# VCO.net
KiCad netlist of a schematic drawn in Altium Designer
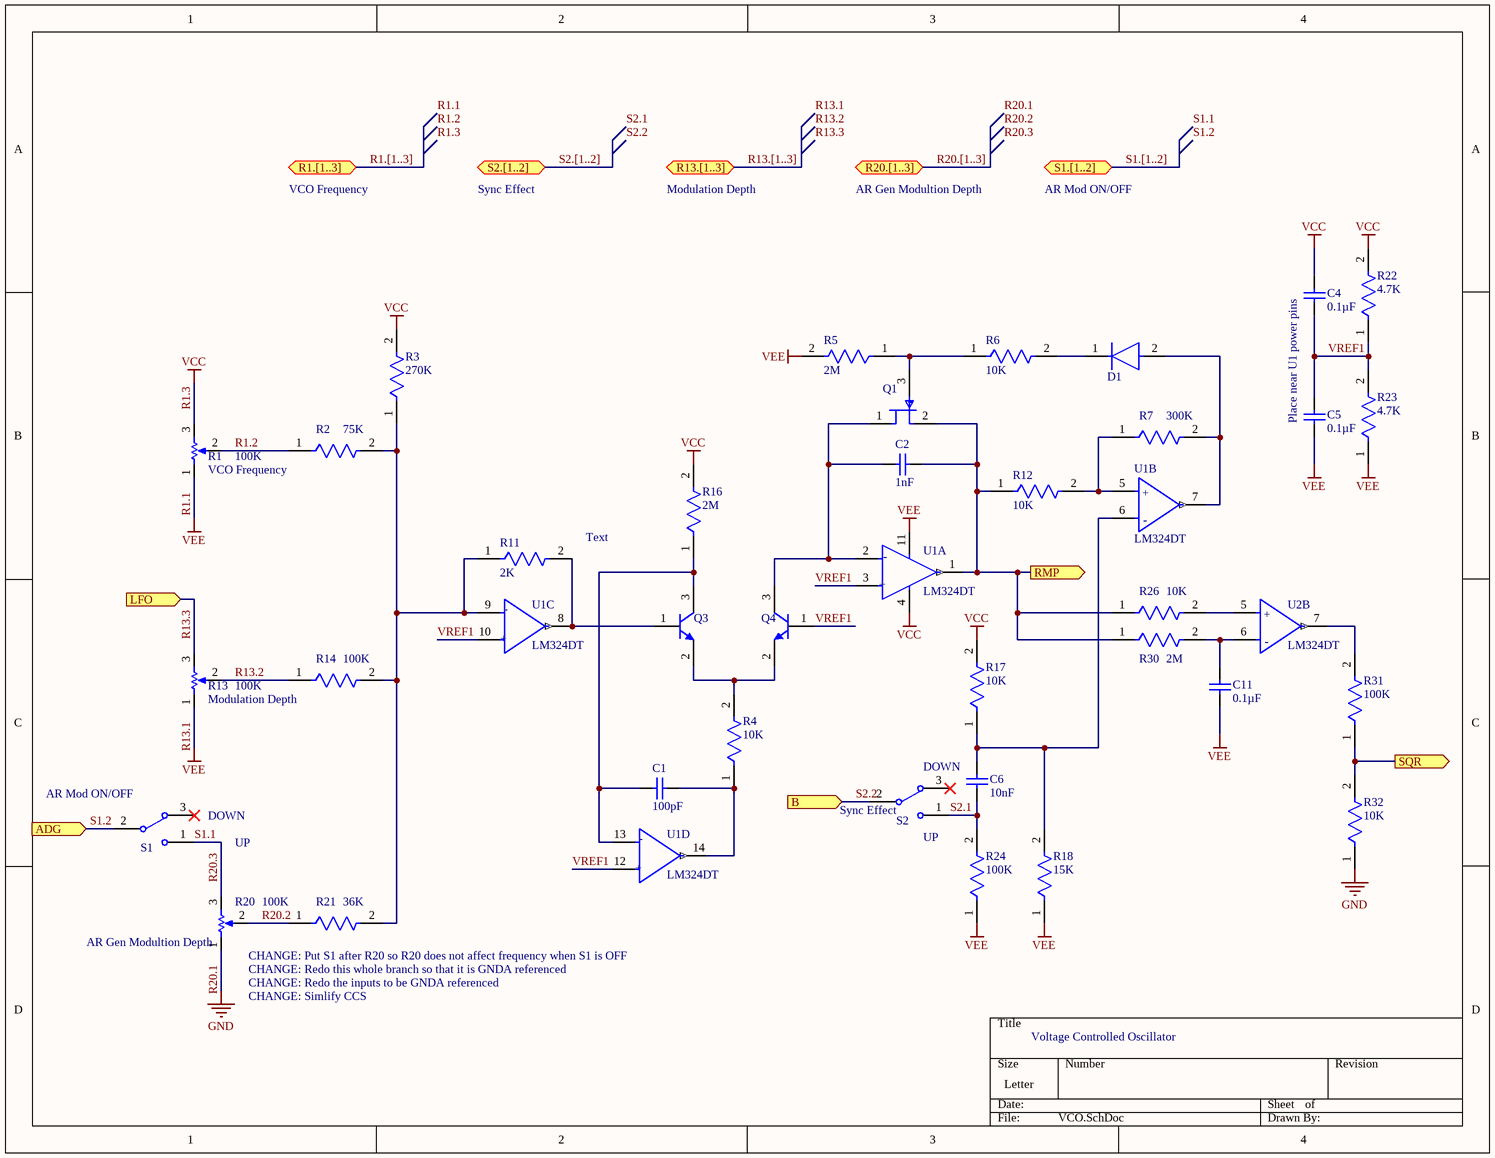
[diagram p0: VCO.SchDoc]

(export (version "E")
  (design (tool "Eeschema 10.0.6"))
  (components
    (comp (ref "C1")
      (value "885012206077‎")
      (footprint "CAPC1608X90X35NL10T15")
      (fields
        (field (name "PART NUMBER") "885012206083‎")
        (field (name "MANUFACTURER") "Wurth")
        (field (name "MANUFACTURER PART NUMBER") "885012206083")
        (field (name "CAPACITANCE") "100pF")
      )
      (libsource (lib "Altium Content Vault") (part "CAP"))
    )
    (comp (ref "C2")
      (value "885012206083‎")
      (footprint "CAPC1608X90X35NL10T15")
      (fields
        (field (name "MANUFACTURER") "Wurth")
        (field (name "MANUFACTURER PART NUMBER") "885012206083")
        (field (name "CAPACITANCE") "1nF")
        (field (name "TOLERANCE") "10%")
      )
      (libsource (lib "Altium Content Vault") (part "CAP"))
    )
    (comp (ref "C4")
      (value "CL10B104KB8NNNC")
      (footprint "SAMS-C0603-2_M")
      (description "Multi-layer Ceramic Capacitor, -55 to 125 degC, 2-Pin SMD (0603), RoHS, Tape and Reel")
      (fields (field (name "CAPACITANCE") "0.1µF") (field (name "MANUFACTURER") "Samsung Electro-Mechanics"))
      (libsource (lib "Altium Content Vault") (part "CAP-NP-2"))
    )
    (comp (ref "C5")
      (value "CL10B104KB8NNNC")
      (footprint "SAMS-C0603-2_M")
      (description "Multi-layer Ceramic Capacitor, -55 to 125 degC, 2-Pin SMD (0603), RoHS, Tape and Reel")
      (fields (field (name "CAPACITANCE") "0.1µF") (field (name "MANUFACTURER") "Samsung Electro-Mechanics"))
      (libsource (lib "Altium Content Vault") (part "CAP-NP-2"))
    )
    (comp (ref "C6")
      (value "885012206089")
      (footprint "CAPC1608X90X35NL10T15")
      (fields
        (field (name "MANUFACTURER") "Wurth Electronics")
        (field (name "CAPACITANCE") "10nF")
        (field (name "TOLERANCE") "10%")
      )
      (libsource (lib "Altium Content Vault") (part "CAP"))
    )
    (comp (ref "C11")
      (value "CL10B104KB8NNNC")
      (footprint "SAMS-C0603-2_M")
      (description "Multi-layer Ceramic Capacitor, -55 to 125 degC, 2-Pin SMD (0603), RoHS, Tape and Reel")
      (fields (field (name "CAPACITANCE") "0.1µF") (field (name "MANUFACTURER") "Samsung Electro-Mechanics"))
      (libsource (lib "Altium Content Vault") (part "CAP-NP-2"))
    )
    (comp (ref "D1")
      (value "1N4448WS-7-F")
      (footprint "FP-SOD323-MFG")
      (description "DIODE GEN PURP 75V 250MA SOD323")
      (fields
        (field (name "MANUFACTURER") "Diodes Incorporated")
        (field (name "OCTOPART") "https://octopart.com/1n4448ws-7-f-diodes+inc.-55389585")
      )
      (libsource (lib "Altium Content Vault") (part "d7152d700b627762746794eb795d46e"))
    )
    (comp (ref "Q1")
      (value "MMBFJ113")
      (footprint "FP-318BM-IPC_C")
      (description "JFET N-CH 35V 350MW SOT23")
      (fields
        (field (name "MANUFACTURER") "ON Semiconductor")
        (field (name "OCTOPART") "https://octopart.com/mmbfj113-on+semiconductor-84330253")
      )
      (libsource (lib "Altium Content Vault") (part "14398f7355be6f33287877db3ee21c7"))
    )
    (comp (ref "Q3")
      (value "MMBT3904LT1G")
      (footprint "ONSC-SOT-23-3-318-08_V")
      (description "General Purpose Transistor, NPN Silicon, 3-Pin SOT-23, Pb-Free, Tape and Reel")
      (fields
        (field (name "MANUFACTURER") "On Semiconductor")
        (field (name "MANUFACTURER PART NUMBER") "MMBT3904,215")
      )
      (libsource (lib "Altium Content Vault") (part "ONSC-NPN-B1E2C3-3"))
    )
    (comp (ref "Q4")
      (value "MMBT3904LT1G")
      (footprint "ONSC-SOT-23-3-318-08_V")
      (description "General Purpose Transistor, NPN Silicon, 3-Pin SOT-23, Pb-Free, Tape and Reel")
      (fields
        (field (name "MANUFACTURER") "On Semiconductor")
        (field (name "MANUFACTURER PART NUMBER") "MMBT3904,215")
      )
      (libsource (lib "Altium Content Vault") (part "ONSC-NPN-B1E2C3-3"))
    )
    (comp (ref "R1")
      (value "VCO Frequency")
      (footprint "VR5")
      (description "Potentiometer")
      (fields (field (name "ALTIUM_VALUE") "100K") (field (name "PUBLISHER") "Altium Limited"))
      (libsource (lib "Miscellaneous Devices") (part "RPot"))
    )
    (comp (ref "R2")
      (value "ESR03EZPJ753")
      (footprint "FP-ESR03-IPC_B")
      (description "75kΩ ±5% 0.25W 0603 Anti-Surge Chip Resistor AEC-Q200")
      (fields (field (name "TOLERANCE") "5%") (field (name "RESISTANCE") "75K"))
      (libsource (lib "Altium Content Vault") (part "1029c3af85768c4190bb7ad29bc67b5"))
    )
    (comp (ref "R3")
      (value "ESR03EZPJ274")
      (footprint "FP-ESR03-IPC_B")
      (description "270kΩ ±5% 0.25W 0603 Anti-Surge Chip Resistor AEC-Q200")
      (fields (field (name "RESISTANCE") "270K") (field (name "TOLERANCE") "5%"))
      (libsource (lib "Altium Content Vault") (part "1029c3af85768c4190bb7ad29bc67b5"))
    )
    (comp (ref "R4")
      (value "ESR03EZPJ103")
      (footprint "FP-ESR03-IPC_B")
      (description "10kΩ ±5% 0.25W 0603 Anti-Surge Chip Resistor AEC-Q200")
      (fields (field (name "TOLERANCE") "5%") (field (name "RESISTANCE") "10K"))
      (libsource (lib "Altium Content Vault") (part "1029c3af85768c4190bb7ad29bc67b5"))
    )
    (comp (ref "R5")
      (value "ESR03EZPJ205")
      (footprint "FP-ESR03-IPC_B")
      (description "2MΩ ±5% 0.25W 0603 Anti-Surge Chip Resistor AEC-Q200")
      (fields (field (name "TOLERANCE") "5%") (field (name "RESISTANCE") "2M"))
      (libsource (lib "Altium Content Vault") (part "1029c3af85768c4190bb7ad29bc67b5"))
    )
    (comp (ref "R6")
      (value "ESR03EZPJ103")
      (footprint "FP-ESR03-IPC_B")
      (description "10kΩ ±5% 0.25W 0603 Anti-Surge Chip Resistor AEC-Q200")
      (fields (field (name "TOLERANCE") "5%") (field (name "RESISTANCE") "10K"))
      (libsource (lib "Altium Content Vault") (part "1029c3af85768c4190bb7ad29bc67b5"))
    )
    (comp (ref "R7")
      (value "ESR03EZPJ304")
      (footprint "FP-ESR03-IPC_B")
      (description "300kΩ ±5% 0.25W 0603 Anti-Surge Chip Resistor AEC-Q200")
      (fields (field (name "TOLERANCE") "5%") (field (name "RESISTANCE") "300K"))
      (libsource (lib "Altium Content Vault") (part "1029c3af85768c4190bb7ad29bc67b5"))
    )
    (comp (ref "R11")
      (value "ESR03EZPJ202")
      (footprint "FP-ESR03-IPC_B")
      (description "2kΩ ±5% 0.25W 0603 Anti-Surge Chip Resistor AEC-Q200")
      (fields (field (name "RESISTANCE") "2K") (field (name "TOLERANCE") "5%"))
      (libsource (lib "Altium Content Vault") (part "1029c3af85768c4190bb7ad29bc67b5"))
    )
    (comp (ref "R12")
      (value "ESR03EZPJ103")
      (footprint "FP-ESR03-IPC_B")
      (description "10kΩ ±5% 0.25W 0603 Anti-Surge Chip Resistor AEC-Q200")
      (fields (field (name "TOLERANCE") "5%") (field (name "RESISTANCE") "10K"))
      (libsource (lib "Altium Content Vault") (part "1029c3af85768c4190bb7ad29bc67b5"))
    )
    (comp (ref "R13")
      (value "Modulation Depth")
      (footprint "VR5")
      (description "Potentiometer")
      (fields (field (name "ALTIUM_VALUE") "100K") (field (name "PUBLISHER") "Altium Limited"))
      (libsource (lib "Miscellaneous Devices") (part "RPot"))
    )
    (comp (ref "R14")
      (value "ESR03EZPJ104")
      (footprint "FP-ESR03-IPC_B")
      (description "100kΩ ±5% 0.25W 0603 Anti-Surge Chip Resistor AEC-Q200")
      (fields (field (name "TOLERANCE") "5%") (field (name "RESISTANCE") "100K"))
      (libsource (lib "Altium Content Vault") (part "1029c3af85768c4190bb7ad29bc67b5"))
    )
    (comp (ref "R16")
      (value "ESR03EZPJ205")
      (footprint "FP-ESR03-IPC_B")
      (description "2MΩ ±5% 0.25W 0603 Anti-Surge Chip Resistor AEC-Q200")
      (fields (field (name "TOLERANCE") "5%") (field (name "RESISTANCE") "2M"))
      (libsource (lib "Altium Content Vault") (part "1029c3af85768c4190bb7ad29bc67b5"))
    )
    (comp (ref "R17")
      (value "ESR03EZPJ103")
      (footprint "FP-ESR03-IPC_B")
      (description "10kΩ ±5% 0.25W 0603 Anti-Surge Chip Resistor AEC-Q200")
      (fields (field (name "TOLERANCE") "5%") (field (name "RESISTANCE") "10K"))
      (libsource (lib "Altium Content Vault") (part "1029c3af85768c4190bb7ad29bc67b5"))
    )
    (comp (ref "R18")
      (value "ESR03EZPJ153")
      (footprint "FP-ESR03-IPC_B")
      (description "15kΩ ±5% 0.25W 0603 Anti-Surge Chip Resistor AEC-Q200")
      (fields (field (name "RESISTANCE") "15K") (field (name "TOLERANCE") "5%"))
      (libsource (lib "Altium Content Vault") (part "1029c3af85768c4190bb7ad29bc67b5"))
    )
    (comp (ref "R20")
      (value "AR Gen Modultion Depth")
      (footprint "VR5")
      (description "Potentiometer")
      (fields (field (name "ALTIUM_VALUE") "100K") (field (name "PUBLISHER") "Altium Limited"))
      (libsource (lib "Miscellaneous Devices") (part "RPot"))
    )
    (comp (ref "R21")
      (value "ESR03EZPJ363")
      (footprint "FP-ESR03-IPC_B")
      (description "36kΩ ±5% 0.25W 0603 Anti-Surge Chip Resistor AEC-Q200")
      (fields (field (name "TOLERANCE") "5%") (field (name "RESISTANCE") "36K"))
      (libsource (lib "Altium Content Vault") (part "1029c3af85768c4190bb7ad29bc67b5"))
    )
    (comp (ref "R22")
      (value "ESR03EZPJ472")
      (footprint "FP-ESR03-IPC_B")
      (description "4.7kΩ ±5% 0.25W 0603 Anti-Surge Chip Resistor AEC-Q200")
      (fields (field (name "TOLERANCE") "5%") (field (name "RESISTANCE") "4.7K"))
      (libsource (lib "Altium Content Vault") (part "1029c3af85768c4190bb7ad29bc67b5"))
    )
    (comp (ref "R23")
      (value "ESR03EZPJ472")
      (footprint "FP-ESR03-IPC_B")
      (description "4.7kΩ ±5% 0.25W 0603 Anti-Surge Chip Resistor AEC-Q200")
      (fields (field (name "TOLERANCE") "5%") (field (name "RESISTANCE") "4.7K"))
      (libsource (lib "Altium Content Vault") (part "1029c3af85768c4190bb7ad29bc67b5"))
    )
    (comp (ref "R24")
      (value "ESR03EZPJ104")
      (footprint "FP-ESR03-IPC_B")
      (description "100kΩ ±5% 0.25W 0603 Anti-Surge Chip Resistor AEC-Q200")
      (fields (field (name "TOLERANCE") "5%") (field (name "RESISTANCE") "100K"))
      (libsource (lib "Altium Content Vault") (part "1029c3af85768c4190bb7ad29bc67b5"))
    )
    (comp (ref "R26")
      (value "ESR03EZPJ103")
      (footprint "FP-ESR03-IPC_B")
      (description "10kΩ ±5% 0.25W 0603 Anti-Surge Chip Resistor AEC-Q200")
      (fields (field (name "TOLERANCE") "5%") (field (name "RESISTANCE") "10K"))
      (libsource (lib "Altium Content Vault") (part "1029c3af85768c4190bb7ad29bc67b5"))
    )
    (comp (ref "R30")
      (value "ESR03EZPJ205")
      (footprint "FP-ESR03-IPC_B")
      (description "2MΩ ±5% 0.25W 0603 Anti-Surge Chip Resistor AEC-Q200")
      (fields (field (name "TOLERANCE") "5%") (field (name "RESISTANCE") "2M"))
      (libsource (lib "Altium Content Vault") (part "1029c3af85768c4190bb7ad29bc67b5"))
    )
    (comp (ref "R31")
      (value "ESR03EZPJ104")
      (footprint "FP-ESR03-IPC_B")
      (description "100kΩ ±5% 0.25W 0603 Anti-Surge Chip Resistor AEC-Q200")
      (fields (field (name "TOLERANCE") "5%") (field (name "RESISTANCE") "100K"))
      (libsource (lib "Altium Content Vault") (part "1029c3af85768c4190bb7ad29bc67b5"))
    )
    (comp (ref "R32")
      (value "ESR03EZPJ103")
      (footprint "FP-ESR03-IPC_B")
      (description "10kΩ ±5% 0.25W 0603 Anti-Surge Chip Resistor AEC-Q200")
      (fields (field (name "TOLERANCE") "5%") (field (name "RESISTANCE") "10K"))
      (libsource (lib "Altium Content Vault") (part "1029c3af85768c4190bb7ad29bc67b5"))
    )
    (comp (ref "S1")
      (value "AR Mod ON/OFF")
      (footprint "HDR1X3")
      (description "Switch Toggle ON None ON SPDT Round Lever Solder Lug 5A 250VAC 28VDC Panel Mount with Threads")
      (fields
        (field (name "MANUFACTURER") "E-Switch")
        (field (name "MANUFACTURER PART NUMBER") "100SP1T1B1M1QEH")
      )
      (libsource (lib "Miscellaneous Devices") (part "SW-SPDT"))
    )
    (comp (ref "S2")
      (value "Sync Effect")
      (footprint "HDR1X3")
      (description "Switch Toggle ON None ON SPDT Round Lever Solder Lug 5A 250VAC 28VDC Panel Mount with Threads")
      (fields
        (field (name "MANUFACTURER") "E-Switch")
        (field (name "MANUFACTURER PART NUMBER") "100SP1T1B1M1QEH")
      )
      (libsource (lib "Miscellaneous Devices") (part "SW-SPDT"))
    )
    (comp (ref "U1")
      (value "LM324DT")
      (footprint "FP-SO-14-MFG")
      (description "IC OPAMP GP 4 CIRCUIT 14SO")
      (fields
        (field (name "OCTOPART") "https://octopart.com/lm324dt-stmicroelectronics-39579146")
        (field (name "MANUFACTURER") "STMicroelectronics")
      )
      (libsource (lib "Altium Content Vault") (part "a065ef67e5aa9ef3942d43d6008d043"))
    )
    (comp (ref "U2")
      (value "LM324DT")
      (footprint "FP-SO-14-MFG")
      (description "IC OPAMP GP 4 CIRCUIT 14SO")
      (fields
        (field (name "OCTOPART") "https://octopart.com/lm324dt-stmicroelectronics-39579146")
        (field (name "MANUFACTURER") "STMicroelectronics")
      )
      (libsource (lib "Altium Content Vault") (part "a065ef67e5aa9ef3942d43d6008d043"))
    )
  )
  (nets
    (net (code "1") (name "/R1.2") (class "Default")
      (node (ref "R1") (pin "2") (pinfunction "TAP_2") (pintype "passive"))
      (node (ref "R2") (pin "1") (pinfunction "1_1") (pintype "passive"))
    )
    (net (code "3") (name "/R13.2") (class "Default")
      (node (ref "R13") (pin "2") (pinfunction "TAP_2") (pintype "passive"))
      (node (ref "R14") (pin "1") (pinfunction "1_1") (pintype "passive"))
    )
    (net (code "4") (name "/R13.3") (class "Default")
      (node (ref "R13") (pin "3") (pinfunction "BOT_3") (pintype "passive"))
    )
    (net (code "6") (name "/R20.2") (class "Default")
      (node (ref "R20") (pin "2") (pinfunction "TAP_2") (pintype "passive"))
      (node (ref "R21") (pin "1") (pinfunction "1_1") (pintype "passive"))
    )
    (net (code "8") (name "/RMP") (class "Default")
      (node (ref "C2") (pin "2") (pinfunction "2_2") (pintype "passive"))
      (node (ref "Q1") (pin "2") (pinfunction "S_2") (pintype "passive"))
      (node (ref "R12") (pin "1") (pinfunction "1_1") (pintype "passive"))
      (node (ref "R26") (pin "1") (pinfunction "1_1") (pintype "passive"))
      (node (ref "R30") (pin "1") (pinfunction "1_1") (pintype "passive"))
      (node (ref "U1") (pin "1") (pinfunction "Output_1_1") (pintype "output"))
    )
    (net (code "9") (name "/S1.1") (class "Default")
      (node (ref "R20") (pin "3") (pinfunction "BOT_3") (pintype "passive"))
      (node (ref "S1") (pin "1") (pinfunction "1_1") (pintype "passive"))
    )
    (net (code "10") (name "/S1.2") (class "Default")
      (node (ref "S1") (pin "2") (pinfunction "2_2") (pintype "passive"))
    )
    (net (code "12") (name "/S2.1") (class "Default")
      (node (ref "C6") (pin "1") (pinfunction "1_1") (pintype "passive"))
      (node (ref "R24") (pin "2") (pinfunction "2_2") (pintype "passive"))
      (node (ref "S2") (pin "1") (pinfunction "1_1") (pintype "passive"))
    )
    (net (code "13") (name "/S2.2") (class "Default")
      (node (ref "S2") (pin "2") (pinfunction "2_2") (pintype "passive"))
    )
    (net (code "15") (name "/SQR") (class "Default")
      (node (ref "R31") (pin "1") (pinfunction "1_1") (pintype "passive"))
      (node (ref "R32") (pin "2") (pinfunction "2_2") (pintype "passive"))
    )
    (net (code "16") (name "/VREF1") (class "Default")
      (node (ref "C4") (pin "2") (pinfunction "2_2") (pintype "passive"))
      (node (ref "C5") (pin "1") (pinfunction "1_1") (pintype "passive"))
      (node (ref "Q4") (pin "1") (pinfunction "B_1") (pintype "passive"))
      (node (ref "R22") (pin "1") (pinfunction "1_1") (pintype "passive"))
      (node (ref "R23") (pin "2") (pinfunction "2_2") (pintype "passive"))
      (node (ref "U1") (pin "10") (pinfunction "Non-Inverting_Input_3_10") (pintype "tri_state"))
      (node (ref "U1") (pin "12") (pinfunction "Non-Inverting_Input_4_12") (pintype "tri_state"))
      (node (ref "U1") (pin "3") (pinfunction "Non-Inverting_Input_1_3") (pintype "tri_state"))
    )
    (net (code "17") (name "GND") (class "Default")
      (node (ref "R20") (pin "1") (pinfunction "TOP_1") (pintype "passive"))
      (node (ref "R32") (pin "1") (pinfunction "1_1") (pintype "passive"))
    )
    (net (code "18") (name "Net-(D1-A)") (class "Default")
      (node (ref "D1") (pin "2") (pinfunction "A_2") (pintype "passive"))
      (node (ref "R7") (pin "2") (pinfunction "2_2") (pintype "passive"))
      (node (ref "U1") (pin "7") (pinfunction "Output_2_7") (pintype "output"))
    )
    (net (code "19") (name "Net-(D1-C)") (class "Default")
      (node (ref "D1") (pin "1") (pinfunction "C_1") (pintype "passive"))
      (node (ref "R6") (pin "2") (pinfunction "2_2") (pintype "passive"))
    )
    (net (code "20") (name "Net-(Q1-D)") (class "Default")
      (node (ref "C2") (pin "1") (pinfunction "1_1") (pintype "passive"))
      (node (ref "Q1") (pin "1") (pinfunction "D_1") (pintype "passive"))
      (node (ref "Q4") (pin "3") (pinfunction "C_3") (pintype "passive"))
      (node (ref "U1") (pin "2") (pinfunction "Inverting_Input_1_2") (pintype "tri_state"))
    )
    (net (code "21") (name "Net-(Q1-G)") (class "Default")
      (node (ref "Q1") (pin "3") (pinfunction "G_3") (pintype "passive"))
      (node (ref "R5") (pin "1") (pinfunction "1_1") (pintype "passive"))
      (node (ref "R6") (pin "1") (pinfunction "1_1") (pintype "passive"))
    )
    (net (code "22") (name "Net-(Q3-B)") (class "Default")
      (node (ref "Q3") (pin "1") (pinfunction "B_1") (pintype "passive"))
      (node (ref "R11") (pin "2") (pinfunction "2_2") (pintype "passive"))
      (node (ref "U1") (pin "8") (pinfunction "Output_3_8") (pintype "output"))
    )
    (net (code "23") (name "Net-(Q3-C)") (class "Default")
      (node (ref "C1") (pin "1") (pinfunction "1_1") (pintype "passive"))
      (node (ref "Q3") (pin "3") (pinfunction "C_3") (pintype "passive"))
      (node (ref "R16") (pin "1") (pinfunction "1_1") (pintype "passive"))
      (node (ref "U1") (pin "13") (pinfunction "Inverting_Input_4_13") (pintype "tri_state"))
    )
    (net (code "24") (name "Net-(Q3-E)") (class "Default")
      (node (ref "Q3") (pin "2") (pinfunction "E_2") (pintype "passive"))
      (node (ref "Q4") (pin "2") (pinfunction "E_2") (pintype "passive"))
      (node (ref "R4") (pin "2") (pinfunction "2_2") (pintype "passive"))
    )
    (net (code "25") (name "Net-(U1B-Inverting_Input_2)") (class "Default")
      (node (ref "C6") (pin "2") (pinfunction "2_2") (pintype "passive"))
      (node (ref "R17") (pin "1") (pinfunction "1_1") (pintype "passive"))
      (node (ref "R18") (pin "2") (pinfunction "2_2") (pintype "passive"))
      (node (ref "U1") (pin "6") (pinfunction "Inverting_Input_2_6") (pintype "tri_state"))
    )
    (net (code "26") (name "Net-(U1B-Non-Inverting_Input_2)") (class "Default")
      (node (ref "R12") (pin "2") (pinfunction "2_2") (pintype "passive"))
      (node (ref "R7") (pin "1") (pinfunction "1_1") (pintype "passive"))
      (node (ref "U1") (pin "5") (pinfunction "Non-Inverting_Input_2_5") (pintype "tri_state"))
    )
    (net (code "27") (name "Net-(U1C-Inverting_Input_3)") (class "Default")
      (node (ref "R11") (pin "1") (pinfunction "1_1") (pintype "passive"))
      (node (ref "R14") (pin "2") (pinfunction "2_2") (pintype "passive"))
      (node (ref "R2") (pin "2") (pinfunction "2_2") (pintype "passive"))
      (node (ref "R21") (pin "2") (pinfunction "2_2") (pintype "passive"))
      (node (ref "R3") (pin "1") (pinfunction "1_1") (pintype "passive"))
      (node (ref "U1") (pin "9") (pinfunction "Inverting_Input_3_9") (pintype "tri_state"))
    )
    (net (code "28") (name "Net-(U1D-Output_4)") (class "Default")
      (node (ref "C1") (pin "2") (pinfunction "2_2") (pintype "passive"))
      (node (ref "R4") (pin "1") (pinfunction "1_1") (pintype "passive"))
      (node (ref "U1") (pin "14") (pinfunction "Output_4_14") (pintype "output"))
    )
    (net (code "29") (name "Net-(U2B-Inverting_Input_2)") (class "Default")
      (node (ref "C11") (pin "2") (pinfunction "2_2") (pintype "passive"))
      (node (ref "R30") (pin "2") (pinfunction "2_2") (pintype "passive"))
      (node (ref "U2") (pin "6") (pinfunction "Inverting_Input_2_6") (pintype "tri_state"))
    )
    (net (code "30") (name "Net-(U2B-Non-Inverting_Input_2)") (class "Default")
      (node (ref "R26") (pin "2") (pinfunction "2_2") (pintype "passive"))
      (node (ref "U2") (pin "5") (pinfunction "Non-Inverting_Input_2_5") (pintype "tri_state"))
    )
    (net (code "31") (name "Net-(U2B-Output_2)") (class "Default")
      (node (ref "R31") (pin "2") (pinfunction "2_2") (pintype "passive"))
      (node (ref "U2") (pin "7") (pinfunction "Output_2_7") (pintype "output"))
    )
    (net (code "32") (name "VCC") (class "Default")
      (node (ref "C4") (pin "1") (pinfunction "1_1") (pintype "passive"))
      (node (ref "R1") (pin "3") (pinfunction "BOT_3") (pintype "passive"))
      (node (ref "R16") (pin "2") (pinfunction "2_2") (pintype "passive"))
      (node (ref "R17") (pin "2") (pinfunction "2_2") (pintype "passive"))
      (node (ref "R22") (pin "2") (pinfunction "2_2") (pintype "passive"))
      (node (ref "R3") (pin "2") (pinfunction "2_2") (pintype "passive"))
      (node (ref "U1") (pin "4") (pinfunction "VCC+_4") (pintype "power_in"))
    )
    (net (code "33") (name "VEE") (class "Default")
      (node (ref "C11") (pin "1") (pinfunction "1_1") (pintype "passive"))
      (node (ref "C5") (pin "2") (pinfunction "2_2") (pintype "passive"))
      (node (ref "R1") (pin "1") (pinfunction "TOP_1") (pintype "passive"))
      (node (ref "R13") (pin "1") (pinfunction "TOP_1") (pintype "passive"))
      (node (ref "R18") (pin "1") (pinfunction "1_1") (pintype "passive"))
      (node (ref "R23") (pin "1") (pinfunction "1_1") (pintype "passive"))
      (node (ref "R24") (pin "1") (pinfunction "1_1") (pintype "passive"))
      (node (ref "R5") (pin "2") (pinfunction "2_2") (pintype "passive"))
      (node (ref "U1") (pin "11") (pinfunction "VCC-_11") (pintype "power_in"))
    )
    (net (code "34") (name "unconnected-(S1-Pad3)") (class "Default")
      (node (ref "S1") (pin "3") (pinfunction "3_3") (pintype "passive+no_connect"))
    )
    (net (code "35") (name "unconnected-(S2-Pad3)") (class "Default")
      (node (ref "S2") (pin "3") (pinfunction "3_3") (pintype "passive+no_connect"))
    )
  )
)
